# MTX_Tap_an_er_V13_Nopoti.net
KiCad netlist of a schematic drawn in EAGLE
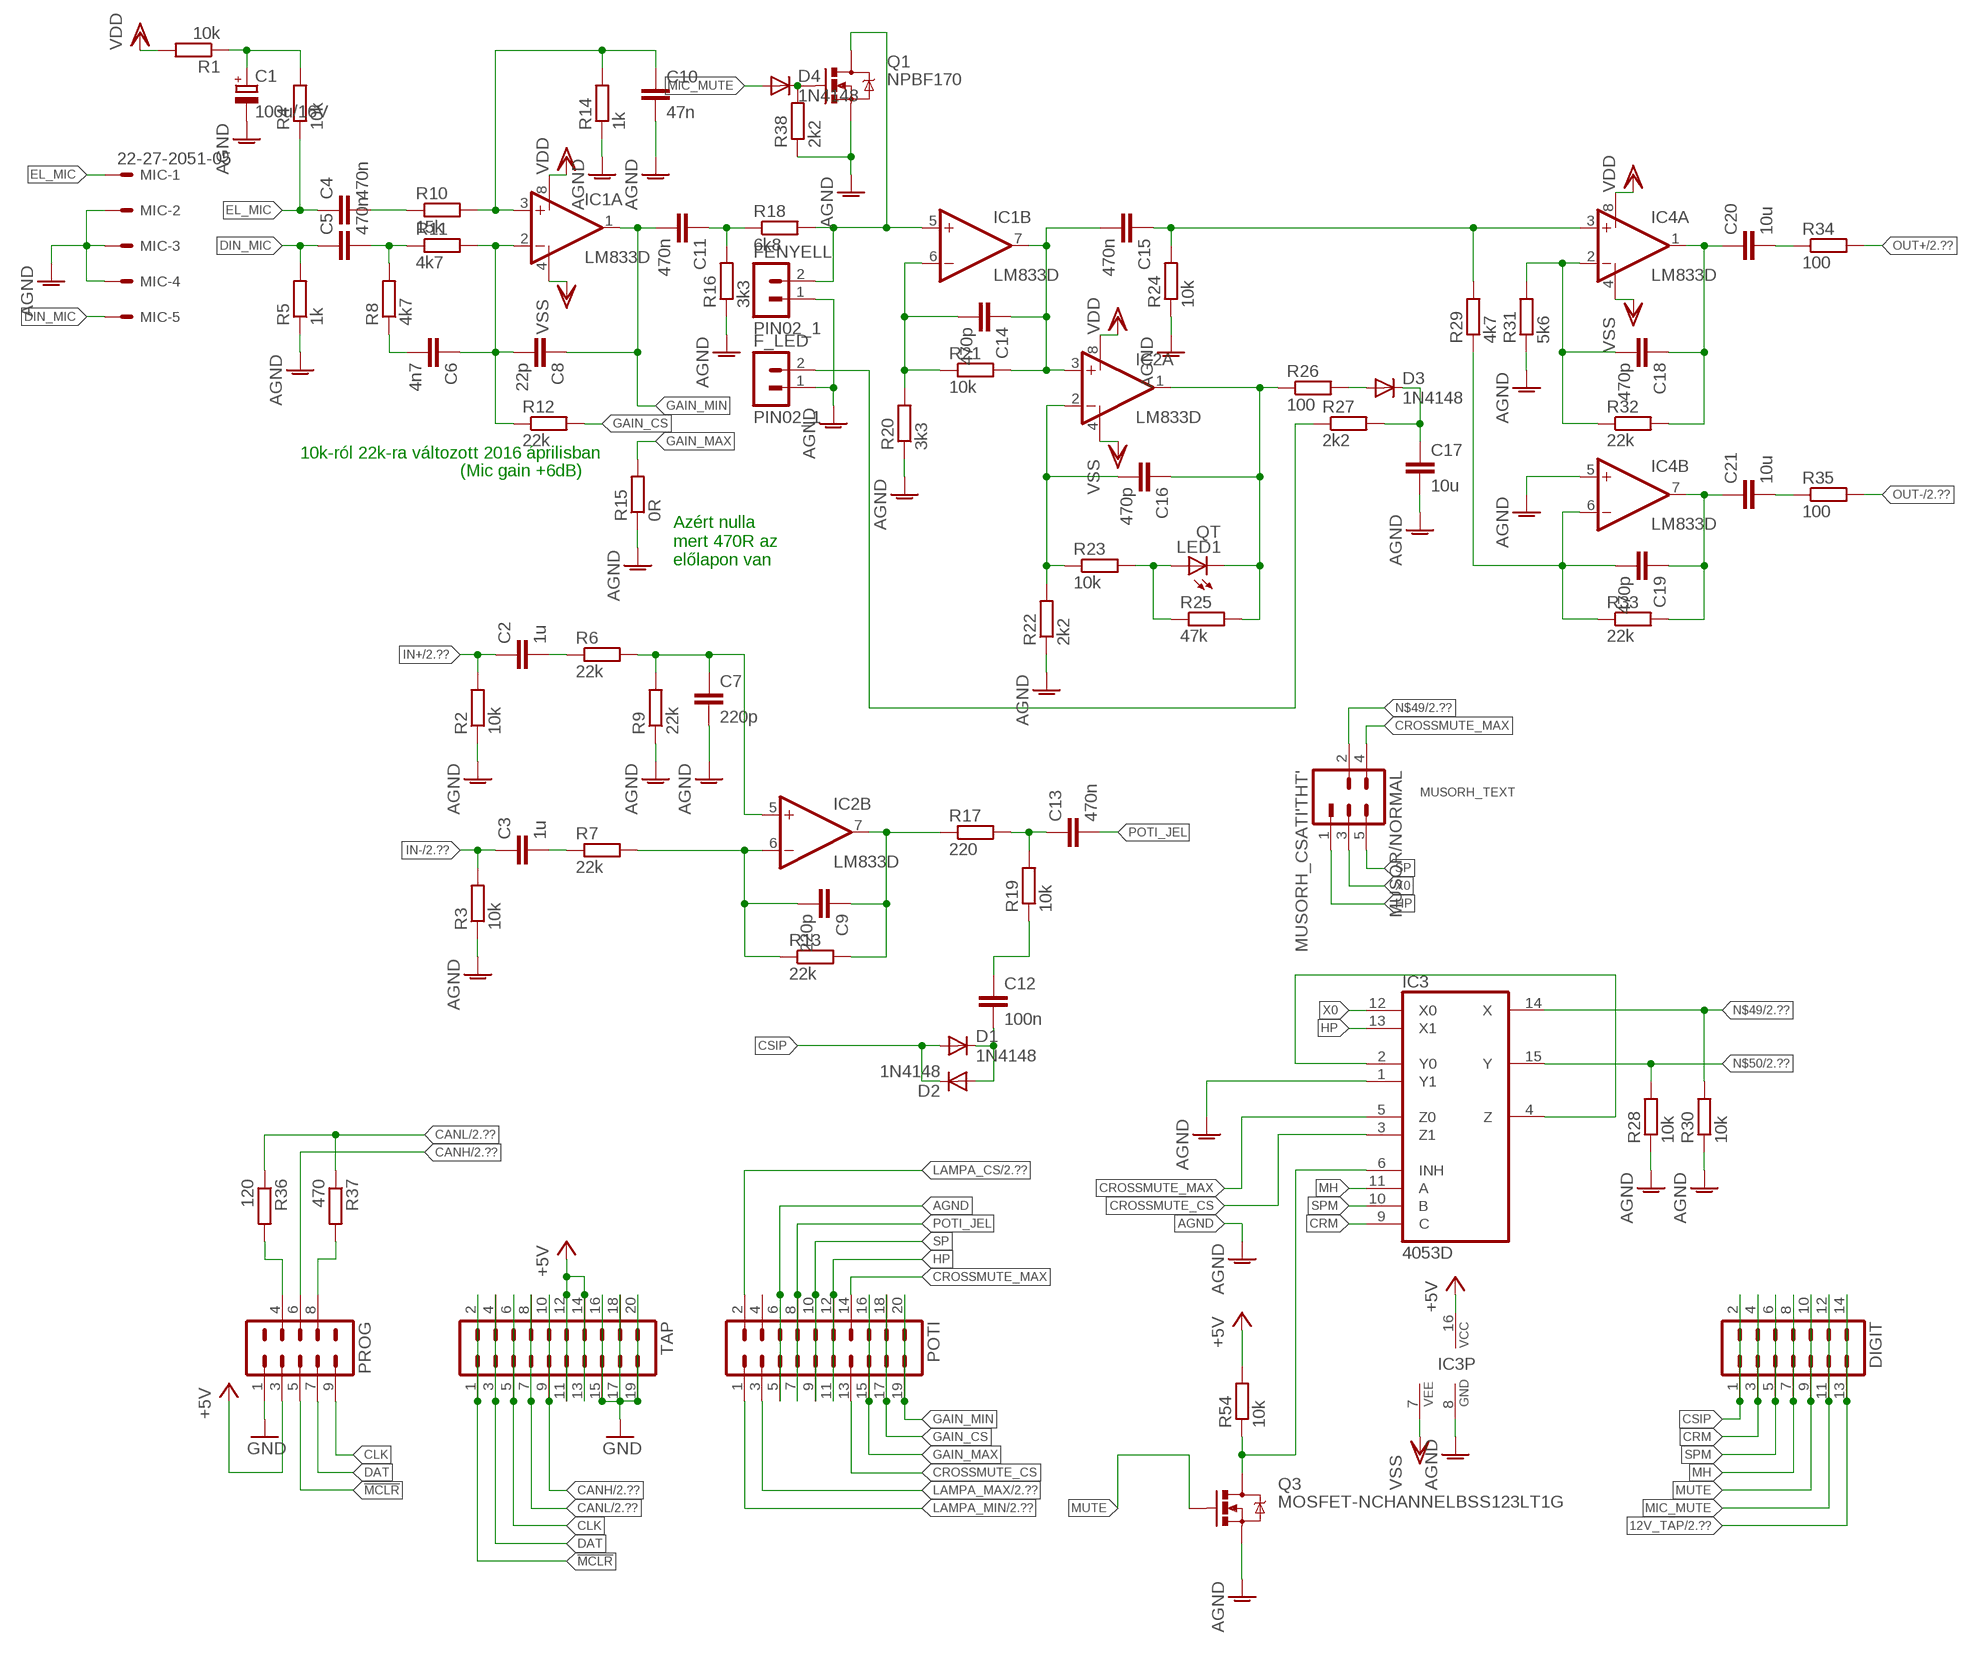
[diagram p0: schematic, sheet 1]
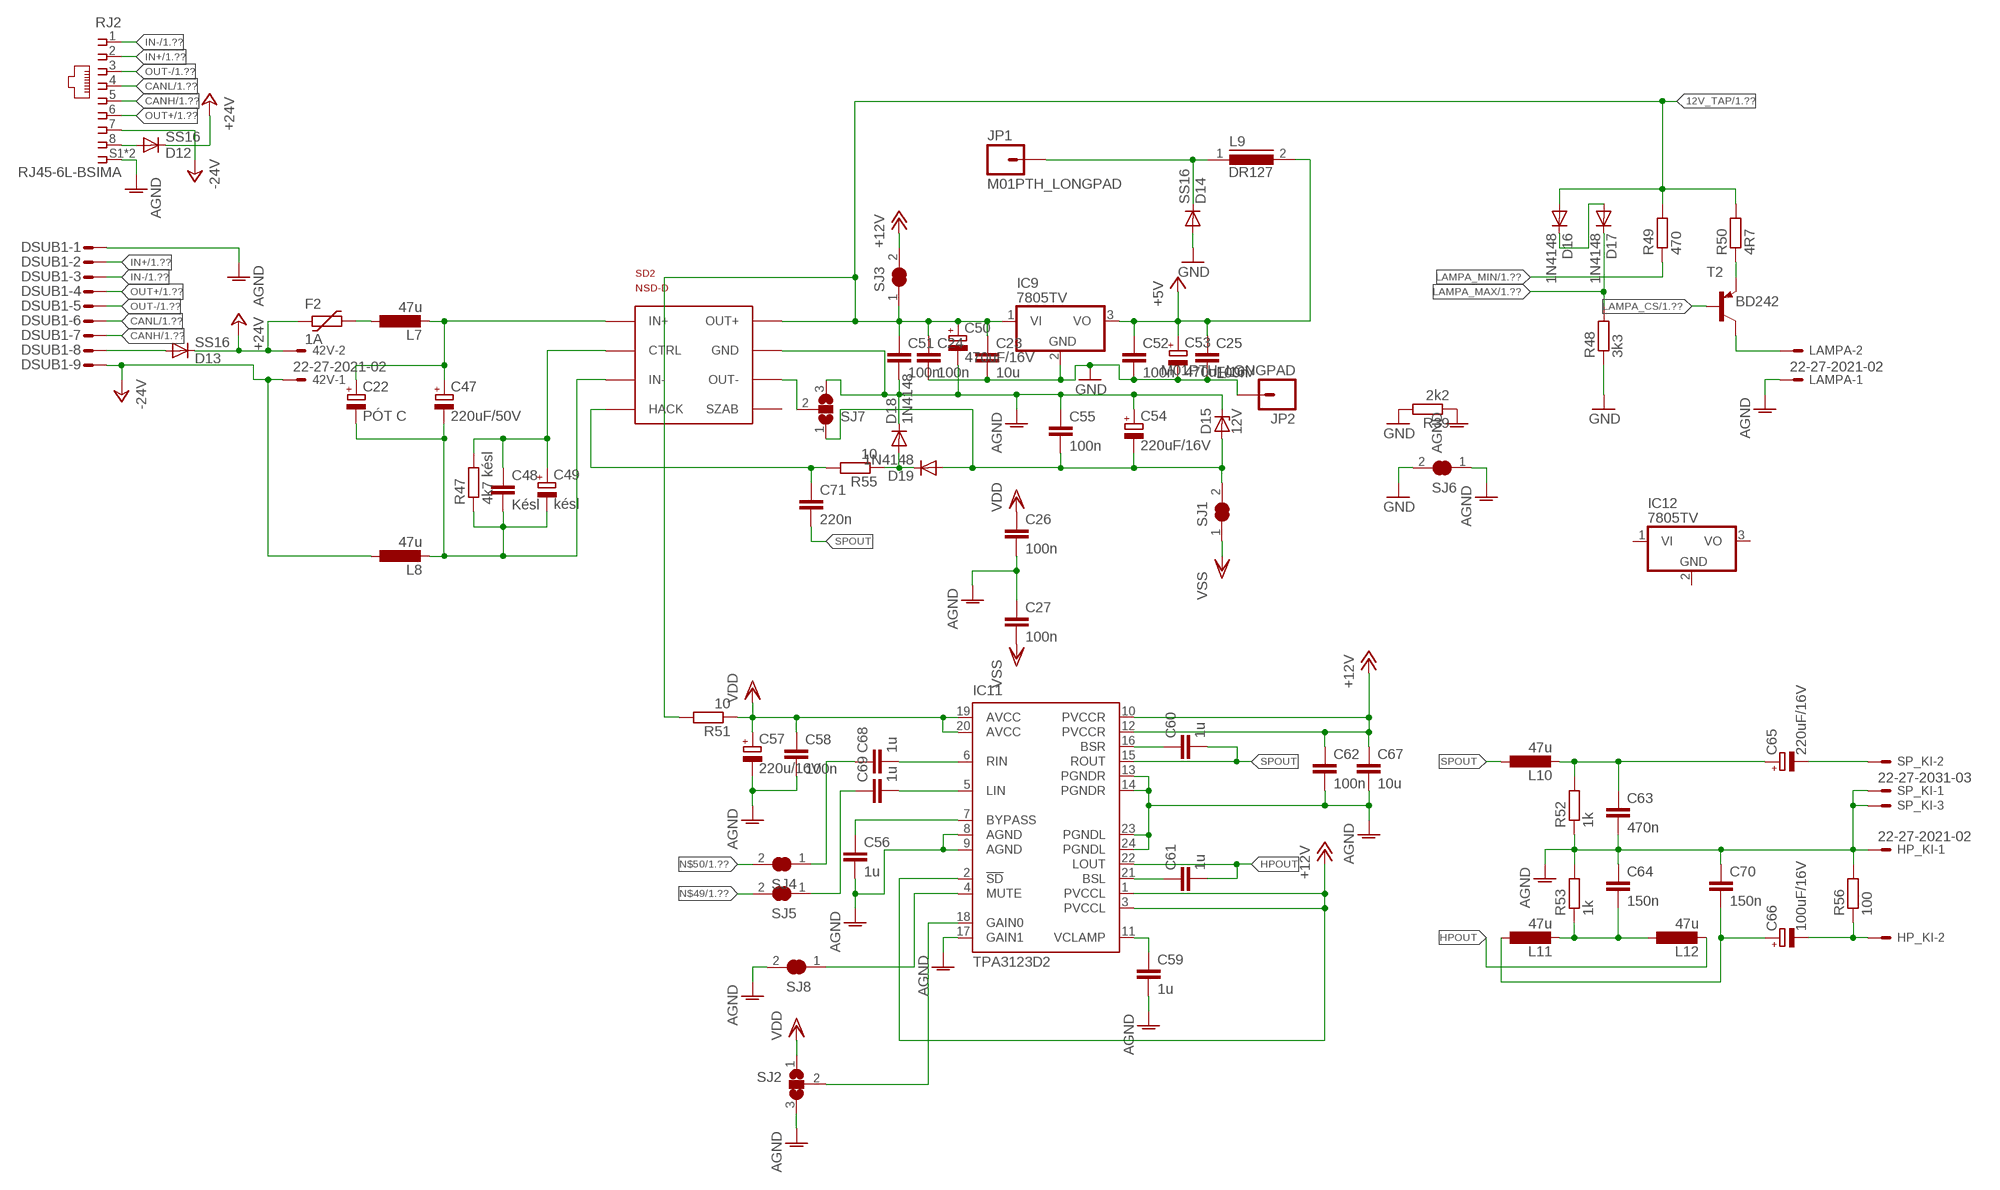
[diagram p1: schematic, sheet 2]

(export (version "E")
  (design (tool "Eeschema 10.0.6"))
  (components
    (comp (ref "42V")
      (value "22-27-2021-02")
      (footprint "eagle-import:6410-02")
      (libsource (lib "eagle-import") (part "22-?-0227-2021"))
    )
    (comp (ref "C22")
      (value "PÓT C")
      (footprint "eagle-import:E3,5-8")
      (libsource (lib "eagle-import") (part "CPOL-EUE3.5-8"))
    )
    (comp (ref "C23")
      (value "10u")
      (footprint "eagle-import:C0805")
      (libsource (lib "eagle-import") (part "C-EUC0805"))
    )
    (comp (ref "C24")
      (value "100n")
      (footprint "eagle-import:C0805")
      (libsource (lib "eagle-import") (part "C-EUC0805"))
    )
    (comp (ref "C25")
      (value "100n")
      (footprint "eagle-import:C0805")
      (libsource (lib "eagle-import") (part "C-EUC0805"))
    )
    (comp (ref "C26")
      (value "100n")
      (footprint "eagle-import:C0805")
      (libsource (lib "eagle-import") (part "C-EUC0805"))
    )
    (comp (ref "C27")
      (value "100n")
      (footprint "eagle-import:C0805")
      (libsource (lib "eagle-import") (part "C-EUC0805"))
    )
    (comp (ref "C47")
      (value "220uF/50V")
      (footprint "eagle-import:E3,5-8")
      (libsource (lib "eagle-import") (part "CPOL-EUE3.5-8"))
    )
    (comp (ref "C48")
      (value "Késl")
      (footprint "eagle-import:C0805")
      (libsource (lib "eagle-import") (part "C-EUC0805"))
    )
    (comp (ref "C49")
      (value "késl")
      (footprint "eagle-import:E2,5-5")
      (libsource (lib "eagle-import") (part "CPOL-EUE2.5-5"))
    )
    (comp (ref "C50")
      (value "470uF/16V")
      (footprint "eagle-import:E3,5-8")
      (libsource (lib "eagle-import") (part "CPOL-EUE3.5-8"))
    )
    (comp (ref "C51")
      (value "100n")
      (footprint "eagle-import:C0805")
      (libsource (lib "eagle-import") (part "C-EUC0805"))
    )
    (comp (ref "C52")
      (value "100n")
      (footprint "eagle-import:C0805")
      (libsource (lib "eagle-import") (part "C-EUC0805"))
    )
    (comp (ref "C53")
      (value "470uF/16V")
      (footprint "eagle-import:E3,5-8")
      (libsource (lib "eagle-import") (part "CPOL-EUE3.5-8"))
    )
    (comp (ref "C54")
      (value "220uF/16V")
      (footprint "eagle-import:E2,5-7")
      (libsource (lib "eagle-import") (part "CPOL-EUE2.5-7"))
    )
    (comp (ref "C55")
      (value "100n")
      (footprint "eagle-import:C0805")
      (libsource (lib "eagle-import") (part "C-EUC0805"))
    )
    (comp (ref "C56")
      (value "1u")
      (footprint "eagle-import:C0805")
      (libsource (lib "eagle-import") (part "C-EUC0805"))
    )
    (comp (ref "C57")
      (value "220u/16V")
      (footprint "eagle-import:E2,5-7")
      (libsource (lib "eagle-import") (part "CPOL-EUE2.5-7"))
    )
    (comp (ref "C58")
      (value "100n")
      (footprint "eagle-import:C0805")
      (libsource (lib "eagle-import") (part "C-EUC0805"))
    )
    (comp (ref "C59")
      (value "1u")
      (footprint "eagle-import:C0805")
      (libsource (lib "eagle-import") (part "C-EUC0805"))
    )
    (comp (ref "C60")
      (value "1u")
      (footprint "eagle-import:C0805")
      (libsource (lib "eagle-import") (part "C-EUC0805"))
    )
    (comp (ref "C61")
      (value "1u")
      (footprint "eagle-import:C0805")
      (libsource (lib "eagle-import") (part "C-EUC0805"))
    )
    (comp (ref "C62")
      (value "100n")
      (footprint "eagle-import:C0805")
      (libsource (lib "eagle-import") (part "C-EUC0805"))
    )
    (comp (ref "C63")
      (value "470n")
      (footprint "eagle-import:C0805")
      (libsource (lib "eagle-import") (part "C-EUC0805"))
    )
    (comp (ref "C64")
      (value "150n")
      (footprint "eagle-import:C0805")
      (libsource (lib "eagle-import") (part "C-EUC0805"))
    )
    (comp (ref "C65")
      (value "220uF/16V")
      (footprint "eagle-import:E2,5-7")
      (libsource (lib "eagle-import") (part "CPOL-EUE2.5-7"))
    )
    (comp (ref "C66")
      (value "100uF/16V")
      (footprint "eagle-import:E2,5-6")
      (libsource (lib "eagle-import") (part "CPOL-EUE2.5-6"))
    )
    (comp (ref "C67")
      (value "10u")
      (footprint "eagle-import:C0805")
      (libsource (lib "eagle-import") (part "C-EUC0805"))
    )
    (comp (ref "C68")
      (value "1u")
      (footprint "eagle-import:C0805")
      (libsource (lib "eagle-import") (part "C-EUC0805"))
    )
    (comp (ref "C69")
      (value "1u")
      (footprint "eagle-import:C0805")
      (libsource (lib "eagle-import") (part "C-EUC0805"))
    )
    (comp (ref "C70")
      (value "150n")
      (footprint "eagle-import:C0805")
      (libsource (lib "eagle-import") (part "C-EUC0805"))
    )
    (comp (ref "C71")
      (value "220n")
      (footprint "eagle-import:C0805")
      (libsource (lib "eagle-import") (part "C-EUC0805"))
    )
    (comp (ref "D12")
      (value "SS16")
      (footprint "eagle-import:DO-214AC")
      (libsource (lib "eagle-import") (part "dp_devices_DIODE-DO-214AC"))
    )
    (comp (ref "D13")
      (value "SS16")
      (footprint "eagle-import:DO-214AC")
      (libsource (lib "eagle-import") (part "dp_devices_DIODE-DO-214AC"))
    )
    (comp (ref "D14")
      (value "SS16")
      (footprint "eagle-import:DO-214AC")
      (libsource (lib "eagle-import") (part "dp_devices_DIODE-DO-214AC"))
    )
    (comp (ref "D15")
      (value "12V")
      (footprint "eagle-import:SOD80C")
      (libsource (lib "eagle-import") (part "ZENER-DIODESOD80C"))
    )
    (comp (ref "D16")
      (value "1N4148")
      (footprint "eagle-import:SOD80C")
      (libsource (lib "eagle-import") (part "DIODE-SOD80C"))
    )
    (comp (ref "D17")
      (value "1N4148")
      (footprint "eagle-import:SOD80C")
      (libsource (lib "eagle-import") (part "DIODE-SOD80C"))
    )
    (comp (ref "D18")
      (value "1N4148")
      (footprint "eagle-import:SOD80C")
      (libsource (lib "eagle-import") (part "DIODE-SOD80C"))
    )
    (comp (ref "D19")
      (value "1N4148")
      (footprint "eagle-import:SOD80C")
      (libsource (lib "eagle-import") (part "DIODE-SOD80C"))
    )
    (comp (ref "DSUB1")
      (value "M09-182S")
      (footprint "eagle-import:182-009-MALE")
      (libsource (lib "eagle-import") (part "M09?S-182"))
    )
    (comp (ref "F2")
      (value "1A")
      (footprint "eagle-import:PTC1812L")
      (libsource (lib "eagle-import") (part "FUSE_PTC-1812"))
    )
    (comp (ref "HP_KI")
      (value "22-27-2021-02")
      (footprint "eagle-import:6410-02")
      (libsource (lib "eagle-import") (part "22-?-0227-2021"))
    )
    (comp (ref "IC9")
      (value "7805TV")
      (footprint "eagle-import:TO220V")
      (libsource (lib "eagle-import") (part "78TV05"))
    )
    (comp (ref "IC11")
      (value "TPA3123D2")
      (footprint "eagle-import:PWP-TSSOP24")
      (fields (field (name "MPN") "TPA3123D2PWP"))
      (libsource (lib "eagle-import") (part "TPA3123D2"))
    )
    (comp (ref "IC12")
      (value "7805TV")
      (footprint "eagle-import:TO220V")
      (libsource (lib "eagle-import") (part "78TV05"))
    )
    (comp (ref "JP1")
      (value "M01PTH_LONGPAD")
      (footprint "eagle-import:1X01_LONGPAD")
      (libsource (lib "eagle-import") (part "M01PTH_LONGPAD"))
    )
    (comp (ref "JP2")
      (value "M01PTH_LONGPAD")
      (footprint "eagle-import:1X01_LONGPAD")
      (libsource (lib "eagle-import") (part "M01PTH_LONGPAD"))
    )
    (comp (ref "L7")
      (value "47u")
      (footprint "eagle-import:PIS2816")
      (libsource (lib "eagle-import") (part "L-EUPIS2816"))
    )
    (comp (ref "L8")
      (value "47u")
      (footprint "eagle-import:PIS2816")
      (libsource (lib "eagle-import") (part "L-EUPIS2816"))
    )
    (comp (ref "L9")
      (value "DR127")
      (footprint "eagle-import:DR127")
      (libsource (lib "eagle-import") (part "DR127"))
    )
    (comp (ref "L10")
      (value "47u")
      (footprint "eagle-import:PIS2816")
      (libsource (lib "eagle-import") (part "L-EUPIS2816"))
    )
    (comp (ref "L11")
      (value "47u")
      (footprint "eagle-import:PIS2816")
      (libsource (lib "eagle-import") (part "L-EUPIS2816"))
    )
    (comp (ref "L12")
      (value "47u")
      (footprint "eagle-import:PIS2816")
      (libsource (lib "eagle-import") (part "L-EUPIS2816"))
    )
    (comp (ref "LAMPA")
      (value "22-27-2021-02")
      (footprint "eagle-import:6410-02")
      (libsource (lib "eagle-import") (part "22-?-0227-2021"))
    )
    (comp (ref "R39")
      (value "2k2")
      (footprint "eagle-import:R0805")
      (libsource (lib "eagle-import") (part "R-EU_R0805"))
    )
    (comp (ref "R47")
      (value "4k7 késl")
      (footprint "eagle-import:R0805")
      (libsource (lib "eagle-import") (part "R-EU_R0805"))
    )
    (comp (ref "R48")
      (value "3k3")
      (footprint "eagle-import:R0805")
      (libsource (lib "eagle-import") (part "R-EU_R0805"))
    )
    (comp (ref "R49")
      (value "470")
      (footprint "eagle-import:R0805")
      (libsource (lib "eagle-import") (part "R-EU_R0805"))
    )
    (comp (ref "R50")
      (value "4R7")
      (footprint "eagle-import:R0805")
      (libsource (lib "eagle-import") (part "R-EU_R0805"))
    )
    (comp (ref "R51")
      (value "10")
      (footprint "eagle-import:R1210")
      (libsource (lib "eagle-import") (part "R-EU_R1210"))
    )
    (comp (ref "R52")
      (value "1k")
      (footprint "eagle-import:R0805")
      (libsource (lib "eagle-import") (part "R-EU_R0805"))
    )
    (comp (ref "R53")
      (value "1k")
      (footprint "eagle-import:R0805")
      (libsource (lib "eagle-import") (part "R-EU_R0805"))
    )
    (comp (ref "R55")
      (value "10")
      (footprint "eagle-import:R0805")
      (libsource (lib "eagle-import") (part "R-EU_R0805"))
    )
    (comp (ref "R56")
      (value "100")
      (footprint "eagle-import:R0805")
      (libsource (lib "eagle-import") (part "R-EU_R0805"))
    )
    (comp (ref "RJ2")
      (value "RJ45-6L-BSIMA")
      (footprint "eagle-import:RJ45")
      (fields (field (name "MPN") "RJ45-6L-B"))
      (libsource (lib "eagle-import") (part "RJ45SIMA-6L-B"))
    )
    (comp (ref "SD2")
      (value "NSD-D")
      (footprint "eagle-import:NSD-D")
      (libsource (lib "eagle-import") (part "NSD-D"))
    )
    (comp (ref "SJ1")
      (value "SOLDERJUMPER_CLOSED")
      (footprint "eagle-import:SOLDERJUMPER_CLOSEDWIRE")
      (libsource (lib "eagle-import") (part "SOLDERJUMPER_CLOSED"))
    )
    (comp (ref "SJ2")
      (value "SJ2WW12")
      (footprint "eagle-import:SJ_2W_12")
      (libsource (lib "eagle-import") (part "SJ2WW12"))
    )
    (comp (ref "SJ3")
      (value "SOLDERJUMPER_CLOSED")
      (footprint "eagle-import:SOLDERJUMPER_CLOSEDWIRE")
      (libsource (lib "eagle-import") (part "SOLDERJUMPER_CLOSED"))
    )
    (comp (ref "SJ4")
      (value "SOLDERJUMPER_CLOSED")
      (footprint "eagle-import:SOLDERJUMPER_CLOSEDWIRE")
      (libsource (lib "eagle-import") (part "SOLDERJUMPER_CLOSED"))
    )
    (comp (ref "SJ5")
      (value "SOLDERJUMPER_CLOSED")
      (footprint "eagle-import:SOLDERJUMPER_CLOSEDWIRE")
      (libsource (lib "eagle-import") (part "SOLDERJUMPER_CLOSED"))
    )
    (comp (ref "SJ6")
      (value "SOLDERJUMPER_CLOSED")
      (footprint "eagle-import:SOLDERJUMPER_CLOSEDWIRE")
      (libsource (lib "eagle-import") (part "SOLDERJUMPER_CLOSED"))
    )
    (comp (ref "SJ7")
      (value "SJ2WW23")
      (footprint "eagle-import:SJ_2W_23")
      (libsource (lib "eagle-import") (part "SJ2WW23"))
    )
    (comp (ref "SJ8")
      (value "SOLDERJUMPER_CLOSED")
      (footprint "eagle-import:SOLDERJUMPER_CLOSEDWIRE")
      (libsource (lib "eagle-import") (part "SOLDERJUMPER_CLOSED"))
    )
    (comp (ref "SP_KI")
      (value "22-27-2031-03")
      (footprint "eagle-import:6410-03")
      (libsource (lib "eagle-import") (part "22-?-0327-2031"))
    )
    (comp (ref "T2")
      (value "BD242")
      (footprint "eagle-import:TO220V")
      (libsource (lib "eagle-import") (part "-PNP-TO220V"))
    )
    (comp (ref "C1")
      (value "100u/16V")
      (footprint "eagle-import:E2,5-5")
      (libsource (lib "eagle-import") (part "CPOL-EUE2.5-5"))
    )
    (comp (ref "C2")
      (value "1u")
      (footprint "eagle-import:C0805")
      (libsource (lib "eagle-import") (part "C-EUC0805"))
    )
    (comp (ref "C3")
      (value "1u")
      (footprint "eagle-import:C0805")
      (libsource (lib "eagle-import") (part "C-EUC0805"))
    )
    (comp (ref "C4")
      (value "470n")
      (footprint "eagle-import:C0805")
      (libsource (lib "eagle-import") (part "C-EUC0805"))
    )
    (comp (ref "C5")
      (value "470n")
      (footprint "eagle-import:C0805")
      (libsource (lib "eagle-import") (part "C-EUC0805"))
    )
    (comp (ref "C6")
      (value "4n7")
      (footprint "eagle-import:C0805")
      (libsource (lib "eagle-import") (part "C-EUC0805"))
    )
    (comp (ref "C7")
      (value "220p")
      (footprint "eagle-import:C0805")
      (libsource (lib "eagle-import") (part "C-EUC0805"))
    )
    (comp (ref "C8")
      (value "22p")
      (footprint "eagle-import:C0805")
      (libsource (lib "eagle-import") (part "C-EUC0805"))
    )
    (comp (ref "C9")
      (value "220p")
      (footprint "eagle-import:C0805")
      (libsource (lib "eagle-import") (part "C-EUC0805"))
    )
    (comp (ref "C10")
      (value "47n")
      (footprint "eagle-import:C0805")
      (libsource (lib "eagle-import") (part "C-EUC0805"))
    )
    (comp (ref "C11")
      (value "470n")
      (footprint "eagle-import:C0805")
      (libsource (lib "eagle-import") (part "C-EUC0805"))
    )
    (comp (ref "C12")
      (value "100n")
      (footprint "eagle-import:C0805")
      (libsource (lib "eagle-import") (part "C-EUC0805"))
    )
    (comp (ref "C13")
      (value "470n")
      (footprint "eagle-import:C0805")
      (libsource (lib "eagle-import") (part "C-EUC0805"))
    )
    (comp (ref "C14")
      (value "470p")
      (footprint "eagle-import:C0805")
      (libsource (lib "eagle-import") (part "C-EUC0805"))
    )
    (comp (ref "C15")
      (value "470n")
      (footprint "eagle-import:C0805")
      (libsource (lib "eagle-import") (part "C-EUC0805"))
    )
    (comp (ref "C16")
      (value "470p")
      (footprint "eagle-import:C0805")
      (libsource (lib "eagle-import") (part "C-EUC0805"))
    )
    (comp (ref "C17")
      (value "10u")
      (footprint "eagle-import:C0805")
      (libsource (lib "eagle-import") (part "C-EUC0805"))
    )
    (comp (ref "C18")
      (value "470p")
      (footprint "eagle-import:C0805")
      (libsource (lib "eagle-import") (part "C-EUC0805"))
    )
    (comp (ref "C19")
      (value "470p")
      (footprint "eagle-import:C0805")
      (libsource (lib "eagle-import") (part "C-EUC0805"))
    )
    (comp (ref "C20")
      (value "10u")
      (footprint "eagle-import:C0805")
      (libsource (lib "eagle-import") (part "C-EUC0805"))
    )
    (comp (ref "C21")
      (value "10u")
      (footprint "eagle-import:C0805")
      (libsource (lib "eagle-import") (part "C-EUC0805"))
    )
    (comp (ref "D1")
      (value "1N4148")
      (footprint "eagle-import:SOD80C")
      (libsource (lib "eagle-import") (part "DIODE-SOD80C"))
    )
    (comp (ref "D2")
      (value "1N4148")
      (footprint "eagle-import:SOD80C")
      (libsource (lib "eagle-import") (part "DIODE-SOD80C"))
    )
    (comp (ref "D3")
      (value "1N4148")
      (footprint "eagle-import:SOD80C")
      (libsource (lib "eagle-import") (part "DIODE-SOD80C"))
    )
    (comp (ref "D4")
      (value "1N4148")
      (footprint "eagle-import:SOD80C")
      (libsource (lib "eagle-import") (part "DIODE-SOD80C"))
    )
    (comp (ref "DIGIT")
      (value "MA07-2")
      (footprint "eagle-import:MA07-2")
      (libsource (lib "eagle-import") (part "MA07-2"))
    )
    (comp (ref "FENYELL")
      (value "PIN02_1")
      (footprint "eagle-import:PIN02_1")
      (libsource (lib "eagle-import") (part "PIN02_1"))
    )
    (comp (ref "F_LED")
      (value "PIN02_1")
      (footprint "eagle-import:PIN02_1")
      (libsource (lib "eagle-import") (part "PIN02_1"))
    )
    (comp (ref "IC1")
      (value "LM833D")
      (footprint "eagle-import:SO08")
      (libsource (lib "eagle-import") (part "LM833D"))
    )
    (comp (ref "IC2")
      (value "LM833D")
      (footprint "eagle-import:SO08")
      (libsource (lib "eagle-import") (part "LM833D"))
    )
    (comp (ref "IC3")
      (value "4053D")
      (footprint "eagle-import:SO16")
      (libsource (lib "eagle-import") (part "4053D"))
    )
    (comp (ref "IC4")
      (value "LM833D")
      (footprint "eagle-import:SO08")
      (libsource (lib "eagle-import") (part "LM833D"))
    )
    (comp (ref "LED1")
      (value "QT")
      (footprint "eagle-import:LED3MM")
      (libsource (lib "eagle-import") (part "LED3MM"))
    )
    (comp (ref "MIC")
      (value "22-27-2051-05")
      (footprint "eagle-import:6410-05")
      (libsource (lib "eagle-import") (part "22-?-0527-2051"))
    )
    (comp (ref "MUSOR/NORMAL")
      (value "MUSORH_CSATI'THT'")
      (footprint "eagle-import:MUSORH_CSATI")
      (libsource (lib "eagle-import") (part "MUSORH_CSATI'THT'"))
    )
    (comp (ref "POTI")
      (value "MA10-2")
      (footprint "eagle-import:MA10-2")
      (libsource (lib "eagle-import") (part "MA10-2"))
    )
    (comp (ref "PROG")
      (value "CN_CANTAN")
      (footprint "eagle-import:CN_CANTAN")
      (libsource (lib "eagle-import") (part "CN_CANTAN"))
    )
    (comp (ref "Q1")
      (value "NPBF170")
      (footprint "eagle-import:SOT23")
      (libsource (lib "eagle-import") (part "MOSFET-NCHANNELBSS138"))
    )
    (comp (ref "Q3")
      (value "MOSFET-NCHANNELBSS123LT1G")
      (footprint "eagle-import:SOT23")
      (libsource (lib "eagle-import") (part "MOSFET-NCHANNELBSS123LT1G"))
    )
    (comp (ref "R1")
      (value "10k")
      (footprint "eagle-import:R0805")
      (libsource (lib "eagle-import") (part "R-EU_R0805"))
    )
    (comp (ref "R2")
      (value "10k")
      (footprint "eagle-import:R0805")
      (libsource (lib "eagle-import") (part "R-EU_R0805"))
    )
    (comp (ref "R3")
      (value "10k")
      (footprint "eagle-import:R0805")
      (libsource (lib "eagle-import") (part "R-EU_R0805"))
    )
    (comp (ref "R4")
      (value "10k")
      (footprint "eagle-import:R0805")
      (libsource (lib "eagle-import") (part "R-EU_R0805"))
    )
    (comp (ref "R5")
      (value "1k")
      (footprint "eagle-import:R0805")
      (libsource (lib "eagle-import") (part "R-EU_R0805"))
    )
    (comp (ref "R6")
      (value "22k")
      (footprint "eagle-import:R0805")
      (libsource (lib "eagle-import") (part "R-EU_R0805"))
    )
    (comp (ref "R7")
      (value "22k")
      (footprint "eagle-import:R0805")
      (libsource (lib "eagle-import") (part "R-EU_R0805"))
    )
    (comp (ref "R8")
      (value "4k7")
      (footprint "eagle-import:R0805")
      (libsource (lib "eagle-import") (part "R-EU_R0805"))
    )
    (comp (ref "R9")
      (value "22k")
      (footprint "eagle-import:R0805")
      (libsource (lib "eagle-import") (part "R-EU_R0805"))
    )
    (comp (ref "R10")
      (value "15k")
      (footprint "eagle-import:R0805")
      (libsource (lib "eagle-import") (part "R-EU_R0805"))
    )
    (comp (ref "R11")
      (value "4k7")
      (footprint "eagle-import:R0805")
      (libsource (lib "eagle-import") (part "R-EU_R0805"))
    )
    (comp (ref "R12")
      (value "22k")
      (footprint "eagle-import:R0805")
      (libsource (lib "eagle-import") (part "R-EU_R0805"))
    )
    (comp (ref "R13")
      (value "22k")
      (footprint "eagle-import:R0805")
      (libsource (lib "eagle-import") (part "R-EU_R0805"))
    )
    (comp (ref "R14")
      (value "1k")
      (footprint "eagle-import:R0805")
      (libsource (lib "eagle-import") (part "R-EU_R0805"))
    )
    (comp (ref "R15")
      (value "0R")
      (footprint "eagle-import:R0805")
      (libsource (lib "eagle-import") (part "R-EU_R0805"))
    )
    (comp (ref "R16")
      (value "3k3")
      (footprint "eagle-import:R0805")
      (libsource (lib "eagle-import") (part "R-EU_R0805"))
    )
    (comp (ref "R17")
      (value "220")
      (footprint "eagle-import:R0805")
      (libsource (lib "eagle-import") (part "R-EU_R0805"))
    )
    (comp (ref "R18")
      (value "6k8")
      (footprint "eagle-import:R0805")
      (libsource (lib "eagle-import") (part "R-EU_R0805"))
    )
    (comp (ref "R19")
      (value "10k")
      (footprint "eagle-import:R0805")
      (libsource (lib "eagle-import") (part "R-EU_R0805"))
    )
    (comp (ref "R20")
      (value "3k3")
      (footprint "eagle-import:R0805")
      (libsource (lib "eagle-import") (part "R-EU_R0805"))
    )
    (comp (ref "R21")
      (value "10k")
      (footprint "eagle-import:R0805")
      (libsource (lib "eagle-import") (part "R-EU_R0805"))
    )
    (comp (ref "R22")
      (value "2k2")
      (footprint "eagle-import:R0805")
      (libsource (lib "eagle-import") (part "R-EU_R0805"))
    )
    (comp (ref "R23")
      (value "10k")
      (footprint "eagle-import:R0805")
      (libsource (lib "eagle-import") (part "R-EU_R0805"))
    )
    (comp (ref "R24")
      (value "10k")
      (footprint "eagle-import:R0805")
      (libsource (lib "eagle-import") (part "R-EU_R0805"))
    )
    (comp (ref "R25")
      (value "47k")
      (footprint "eagle-import:R0805")
      (libsource (lib "eagle-import") (part "R-EU_R0805"))
    )
    (comp (ref "R26")
      (value "100")
      (footprint "eagle-import:R0805")
      (libsource (lib "eagle-import") (part "R-EU_R0805"))
    )
    (comp (ref "R27")
      (value "2k2")
      (footprint "eagle-import:R0805")
      (libsource (lib "eagle-import") (part "R-EU_R0805"))
    )
    (comp (ref "R28")
      (value "10k")
      (footprint "eagle-import:R0805")
      (libsource (lib "eagle-import") (part "R-EU_R0805"))
    )
    (comp (ref "R29")
      (value "4k7")
      (footprint "eagle-import:R0805")
      (libsource (lib "eagle-import") (part "R-EU_R0805"))
    )
    (comp (ref "R30")
      (value "10k")
      (footprint "eagle-import:R0805")
      (libsource (lib "eagle-import") (part "R-EU_R0805"))
    )
    (comp (ref "R31")
      (value "5k6")
      (footprint "eagle-import:R0805")
      (libsource (lib "eagle-import") (part "R-EU_R0805"))
    )
    (comp (ref "R32")
      (value "22k")
      (footprint "eagle-import:R0805")
      (libsource (lib "eagle-import") (part "R-EU_R0805"))
    )
    (comp (ref "R33")
      (value "22k")
      (footprint "eagle-import:R0805")
      (libsource (lib "eagle-import") (part "R-EU_R0805"))
    )
    (comp (ref "R34")
      (value "100")
      (footprint "eagle-import:R0805")
      (libsource (lib "eagle-import") (part "R-EU_R0805"))
    )
    (comp (ref "R35")
      (value "100")
      (footprint "eagle-import:R0805")
      (libsource (lib "eagle-import") (part "R-EU_R0805"))
    )
    (comp (ref "R36")
      (value "120")
      (footprint "eagle-import:R0805")
      (libsource (lib "eagle-import") (part "R-EU_R0805"))
    )
    (comp (ref "R37")
      (value "470")
      (footprint "eagle-import:R0805")
      (libsource (lib "eagle-import") (part "R-EU_R0805"))
    )
    (comp (ref "R38")
      (value "2k2")
      (footprint "eagle-import:R0805")
      (libsource (lib "eagle-import") (part "R-EU_R0805"))
    )
    (comp (ref "R54")
      (value "10k")
      (footprint "eagle-import:R0805")
      (libsource (lib "eagle-import") (part "R-EU_R0805"))
    )
    (comp (ref "TAP")
      (value "MA10-2")
      (footprint "eagle-import:MA10-2")
      (libsource (lib "eagle-import") (part "MA10-2"))
    )
    (comp (ref "U$1")
      (value "MUSORH_TEXT")
      (footprint "eagle-import:MUSORH_TEXT")
      (libsource (lib "eagle-import") (part "MUSORH_TEXT"))
    )
  )
  (nets
    (net (code "1") (name "+5V") (class "Default")
      (node (ref "C25") (pin "1") (pinfunction "1_1") (pintype "passive"))
      (node (ref "C52") (pin "1") (pinfunction "1_1") (pintype "passive"))
      (node (ref "C53") (pin "+") (pinfunction "+_+") (pintype "passive"))
      (node (ref "IC3") (pin "16") (pinfunction "VCC_16") (pintype "power_in"))
      (node (ref "IC9") (pin "3") (pinfunction "VO_3") (pintype "passive"))
      (node (ref "L9") (pin "2") (pinfunction "2_2") (pintype "passive"))
      (node (ref "PROG") (pin "3") (pinfunction "3_3") (pintype "passive"))
      (node (ref "R54") (pin "2") (pinfunction "2_2") (pintype "passive"))
      (node (ref "TAP") (pin "11") (pinfunction "11_11") (pintype "passive"))
      (node (ref "TAP") (pin "12") (pinfunction "12_12") (pintype "passive"))
      (node (ref "TAP") (pin "13") (pinfunction "13_13") (pintype "passive"))
      (node (ref "TAP") (pin "14") (pinfunction "14_14") (pintype "passive"))
    )
    (net (code "2") (name "+12V") (class "Default")
      (node (ref "C62") (pin "1") (pinfunction "1_1") (pintype "passive"))
      (node (ref "C67") (pin "1") (pinfunction "1_1") (pintype "passive"))
      (node (ref "IC11") (pin "1") (pinfunction "PVCCL_1") (pintype "input"))
      (node (ref "IC11") (pin "10") (pinfunction "PVCCR_10") (pintype "input"))
      (node (ref "IC11") (pin "12") (pinfunction "PVCCR_12") (pintype "input"))
      (node (ref "IC11") (pin "2") (pinfunction "~{SD}_2") (pintype "input"))
      (node (ref "IC11") (pin "3") (pinfunction "PVCCL_3") (pintype "input"))
      (node (ref "SJ3") (pin "2") (pinfunction "2_2") (pintype "passive"))
    )
    (net (code "3") (name "+24V") (class "Default")
      (node (ref "42V") (pin "2") (pinfunction "S_2") (pintype "passive"))
      (node (ref "D12") (pin "1") (pinfunction "C_1") (pintype "passive"))
      (node (ref "D13") (pin "1") (pinfunction "C_1") (pintype "passive"))
      (node (ref "F2") (pin "1") (pinfunction "1_1") (pintype "passive"))
    )
    (net (code "4") (name "-24V") (class "Default")
      (node (ref "42V") (pin "1") (pinfunction "S_1") (pintype "passive"))
      (node (ref "DSUB1") (pin "9") (pinfunction "M_9") (pintype "passive"))
      (node (ref "L8") (pin "1") (pinfunction "1_1") (pintype "passive"))
      (node (ref "RJ2") (pin "7") (pinfunction "7_7") (pintype "passive"))
    )
    (net (code "5") (name "12V_TAP") (class "Default")
      (node (ref "C23") (pin "1") (pinfunction "1_1") (pintype "passive"))
      (node (ref "C24") (pin "1") (pinfunction "1_1") (pintype "passive"))
      (node (ref "C50") (pin "+") (pinfunction "+_+") (pintype "passive"))
      (node (ref "C51") (pin "1") (pinfunction "1_1") (pintype "passive"))
      (node (ref "D16") (pin "A") (pinfunction "A_A") (pintype "passive"))
      (node (ref "DIGIT") (pin "13") (pinfunction "13_13") (pintype "passive"))
      (node (ref "DIGIT") (pin "14") (pinfunction "14_14") (pintype "passive"))
      (node (ref "IC9") (pin "1") (pinfunction "VI_1") (pintype "input"))
      (node (ref "R49") (pin "2") (pinfunction "2_2") (pintype "passive"))
      (node (ref "R50") (pin "2") (pinfunction "2_2") (pintype "passive"))
      (node (ref "R51") (pin "2") (pinfunction "2_2") (pintype "passive"))
      (node (ref "SD2") (pin "OUT+") (pinfunction "OUT+_OUT+") (pintype "bidirectional"))
      (node (ref "SJ3") (pin "1") (pinfunction "1_1") (pintype "passive"))
    )
    (net (code "6") (name "AGND") (class "Default")
      (node (ref "C1") (pin "-") (pinfunction "-_-") (pintype "passive"))
      (node (ref "C10") (pin "2") (pinfunction "2_2") (pintype "passive"))
      (node (ref "C17") (pin "2") (pinfunction "2_2") (pintype "passive"))
      (node (ref "C26") (pin "2") (pinfunction "2_2") (pintype "passive"))
      (node (ref "C27") (pin "1") (pinfunction "1_1") (pintype "passive"))
      (node (ref "C50") (pin "-") (pinfunction "-_-") (pintype "passive"))
      (node (ref "C51") (pin "2") (pinfunction "2_2") (pintype "passive"))
      (node (ref "C54") (pin "+") (pinfunction "+_+") (pintype "passive"))
      (node (ref "C55") (pin "1") (pinfunction "1_1") (pintype "passive"))
      (node (ref "C56") (pin "2") (pinfunction "2_2") (pintype "passive"))
      (node (ref "C57") (pin "-") (pinfunction "-_-") (pintype "passive"))
      (node (ref "C58") (pin "2") (pinfunction "2_2") (pintype "passive"))
      (node (ref "C59") (pin "2") (pinfunction "2_2") (pintype "passive"))
      (node (ref "C62") (pin "2") (pinfunction "2_2") (pintype "passive"))
      (node (ref "C63") (pin "2") (pinfunction "2_2") (pintype "passive"))
      (node (ref "C64") (pin "1") (pinfunction "1_1") (pintype "passive"))
      (node (ref "C67") (pin "2") (pinfunction "2_2") (pintype "passive"))
      (node (ref "C7") (pin "2") (pinfunction "2_2") (pintype "passive"))
      (node (ref "C70") (pin "1") (pinfunction "1_1") (pintype "passive"))
      (node (ref "D15") (pin "C") (pinfunction "C_C") (pintype "passive"))
      (node (ref "D18") (pin "C") (pinfunction "C_C") (pintype "passive"))
      (node (ref "DSUB1") (pin "1") (pinfunction "M_1") (pintype "passive"))
      (node (ref "FENYELL") (pin "1") (pinfunction "1_1") (pintype "passive"))
      (node (ref "F_LED") (pin "1") (pinfunction "1_1") (pintype "passive"))
      (node (ref "HP_KI") (pin "1") (pinfunction "S_1") (pintype "passive"))
      (node (ref "IC11") (pin "13") (pinfunction "PGNDR_13") (pintype "input"))
      (node (ref "IC11") (pin "14") (pinfunction "PGNDR_14") (pintype "input"))
      (node (ref "IC11") (pin "17") (pinfunction "GAIN1_17") (pintype "input"))
      (node (ref "IC11") (pin "23") (pinfunction "PGNDL_23") (pintype "input"))
      (node (ref "IC11") (pin "24") (pinfunction "PGNDL_24") (pintype "input"))
      (node (ref "IC11") (pin "8") (pinfunction "AGND_8") (pintype "input"))
      (node (ref "IC11") (pin "9") (pinfunction "AGND_9") (pintype "input"))
      (node (ref "IC3") (pin "1") (pinfunction "Y1_1") (pintype "bidirectional"))
      (node (ref "IC3") (pin "8") (pinfunction "GND_8") (pintype "power_in"))
      (node (ref "IC4") (pin "5") (pinfunction "+IN_5") (pintype "input"))
      (node (ref "LAMPA") (pin "1") (pinfunction "S_1") (pintype "passive"))
      (node (ref "MIC") (pin "2") (pinfunction "S_2") (pintype "passive"))
      (node (ref "MIC") (pin "3") (pinfunction "S_3") (pintype "passive"))
      (node (ref "MIC") (pin "4") (pinfunction "S_4") (pintype "passive"))
      (node (ref "POTI") (pin "5") (pinfunction "5_5") (pintype "passive"))
      (node (ref "POTI") (pin "6") (pinfunction "6_6") (pintype "passive"))
      (node (ref "Q1") (pin "2") (pinfunction "S_2") (pintype "passive"))
      (node (ref "Q3") (pin "2") (pinfunction "S_2") (pintype "passive"))
      (node (ref "R14") (pin "1") (pinfunction "1_1") (pintype "passive"))
      (node (ref "R15") (pin "1") (pinfunction "1_1") (pintype "passive"))
      (node (ref "R16") (pin "1") (pinfunction "1_1") (pintype "passive"))
      (node (ref "R2") (pin "1") (pinfunction "1_1") (pintype "passive"))
      (node (ref "R20") (pin "1") (pinfunction "1_1") (pintype "passive"))
      (node (ref "R22") (pin "1") (pinfunction "1_1") (pintype "passive"))
      (node (ref "R24") (pin "1") (pinfunction "1_1") (pintype "passive"))
      (node (ref "R28") (pin "1") (pinfunction "1_1") (pintype "passive"))
      (node (ref "R3") (pin "1") (pinfunction "1_1") (pintype "passive"))
      (node (ref "R30") (pin "1") (pinfunction "1_1") (pintype "passive"))
      (node (ref "R31") (pin "1") (pinfunction "1_1") (pintype "passive"))
      (node (ref "R38") (pin "1") (pinfunction "1_1") (pintype "passive"))
      (node (ref "R39") (pin "1") (pinfunction "1_1") (pintype "passive"))
      (node (ref "R5") (pin "1") (pinfunction "1_1") (pintype "passive"))
      (node (ref "R52") (pin "1") (pinfunction "1_1") (pintype "passive"))
      (node (ref "R53") (pin "2") (pinfunction "2_2") (pintype "passive"))
      (node (ref "R56") (pin "2") (pinfunction "2_2") (pintype "passive"))
      (node (ref "R9") (pin "1") (pinfunction "1_1") (pintype "passive"))
      (node (ref "RJ2") (pin "S1") (pinfunction "S_S1") (pintype "passive"))
      (node (ref "RJ2") (pin "S2") (pinfunction "S_S2") (pintype "passive"))
      (node (ref "SD2") (pin "COMMON") (pinfunction "GND_COMMON") (pintype "bidirectional"))
      (node (ref "SJ2") (pin "3") (pinfunction "3_3") (pintype "passive"))
      (node (ref "SJ6") (pin "1") (pinfunction "1_1") (pintype "passive"))
      (node (ref "SJ7") (pin "3") (pinfunction "3_3") (pintype "passive"))
      (node (ref "SJ8") (pin "2") (pinfunction "2_2") (pintype "passive"))
      (node (ref "SP_KI") (pin "1") (pinfunction "S_1") (pintype "passive"))
      (node (ref "SP_KI") (pin "3") (pinfunction "S_3") (pintype "passive"))
    )
    (net (code "7") (name "CANH") (class "Default")
      (node (ref "DSUB1") (pin "7") (pinfunction "M_7") (pintype "passive"))
      (node (ref "PROG") (pin "6") (pinfunction "6_6") (pintype "passive"))
      (node (ref "RJ2") (pin "5") (pinfunction "5_5") (pintype "passive"))
      (node (ref "TAP") (pin "10") (pinfunction "10_10") (pintype "passive"))
      (node (ref "TAP") (pin "9") (pinfunction "9_9") (pintype "passive"))
    )
    (net (code "8") (name "CANL") (class "Default")
      (node (ref "DSUB1") (pin "6") (pinfunction "M_6") (pintype "passive"))
      (node (ref "R36") (pin "1") (pinfunction "1_1") (pintype "passive"))
      (node (ref "R37") (pin "1") (pinfunction "1_1") (pintype "passive"))
      (node (ref "RJ2") (pin "4") (pinfunction "4_4") (pintype "passive"))
      (node (ref "TAP") (pin "7") (pinfunction "7_7") (pintype "passive"))
      (node (ref "TAP") (pin "8") (pinfunction "8_8") (pintype "passive"))
    )
    (net (code "9") (name "CLK") (class "Default")
      (node (ref "PROG") (pin "9") (pinfunction "9_9") (pintype "passive"))
      (node (ref "TAP") (pin "5") (pinfunction "5_5") (pintype "passive"))
      (node (ref "TAP") (pin "6") (pinfunction "6_6") (pintype "passive"))
    )
    (net (code "10") (name "CRM") (class "Default")
      (node (ref "DIGIT") (pin "3") (pinfunction "3_3") (pintype "passive"))
      (node (ref "DIGIT") (pin "4") (pinfunction "4_4") (pintype "passive"))
      (node (ref "IC3") (pin "9") (pinfunction "C_9") (pintype "input"))
    )
    (net (code "11") (name "CROSSMUTE_CS") (class "Default")
      (node (ref "IC3") (pin "3") (pinfunction "Z1_3") (pintype "bidirectional"))
      (node (ref "POTI") (pin "13") (pinfunction "13_13") (pintype "passive"))
    )
    (net (code "12") (name "CROSSMUTE_MAX") (class "Default")
      (node (ref "IC3") (pin "5") (pinfunction "Z0_5") (pintype "bidirectional"))
      (node (ref "MUSOR/NORMAL") (pin "4") (pinfunction "4_4") (pintype "passive"))
      (node (ref "POTI") (pin "14") (pinfunction "14_14") (pintype "passive"))
    )
    (net (code "13") (name "CSIP") (class "Default")
      (node (ref "D1") (pin "A") (pinfunction "A_A") (pintype "passive"))
      (node (ref "D2") (pin "C") (pinfunction "C_C") (pintype "passive"))
      (node (ref "DIGIT") (pin "1") (pinfunction "1_1") (pintype "passive"))
      (node (ref "DIGIT") (pin "2") (pinfunction "2_2") (pintype "passive"))
    )
    (net (code "14") (name "DAT") (class "Default")
      (node (ref "PROG") (pin "7") (pinfunction "7_7") (pintype "passive"))
      (node (ref "TAP") (pin "3") (pinfunction "3_3") (pintype "passive"))
      (node (ref "TAP") (pin "4") (pinfunction "4_4") (pintype "passive"))
    )
    (net (code "15") (name "DIN_MIC") (class "Default")
      (node (ref "C5") (pin "1") (pinfunction "1_1") (pintype "passive"))
      (node (ref "MIC") (pin "5") (pinfunction "S_5") (pintype "passive"))
      (node (ref "R5") (pin "2") (pinfunction "2_2") (pintype "passive"))
    )
    (net (code "16") (name "EL_MIC") (class "Default")
      (node (ref "C4") (pin "1") (pinfunction "1_1") (pintype "passive"))
      (node (ref "MIC") (pin "1") (pinfunction "S_1") (pintype "passive"))
      (node (ref "R4") (pin "1") (pinfunction "1_1") (pintype "passive"))
    )
    (net (code "17") (name "GAIN_CS") (class "Default")
      (node (ref "POTI") (pin "17") (pinfunction "17_17") (pintype "passive"))
      (node (ref "POTI") (pin "18") (pinfunction "18_18") (pintype "passive"))
      (node (ref "R12") (pin "2") (pinfunction "2_2") (pintype "passive"))
    )
    (net (code "18") (name "GAIN_MAX") (class "Default")
      (node (ref "POTI") (pin "15") (pinfunction "15_15") (pintype "passive"))
      (node (ref "POTI") (pin "16") (pinfunction "16_16") (pintype "passive"))
      (node (ref "R15") (pin "2") (pinfunction "2_2") (pintype "passive"))
    )
    (net (code "19") (name "GAIN_MIN") (class "Default")
      (node (ref "C11") (pin "2") (pinfunction "2_2") (pintype "passive"))
      (node (ref "C8") (pin "1") (pinfunction "1_1") (pintype "passive"))
      (node (ref "IC1") (pin "1") (pinfunction "OUT_1") (pintype "output"))
      (node (ref "POTI") (pin "19") (pinfunction "19_19") (pintype "passive"))
      (node (ref "POTI") (pin "20") (pinfunction "20_20") (pintype "passive"))
    )
    (net (code "20") (name "GND") (class "Default")
      (node (ref "C23") (pin "2") (pinfunction "2_2") (pintype "passive"))
      (node (ref "C24") (pin "2") (pinfunction "2_2") (pintype "passive"))
      (node (ref "C25") (pin "2") (pinfunction "2_2") (pintype "passive"))
      (node (ref "C52") (pin "2") (pinfunction "2_2") (pintype "passive"))
      (node (ref "C53") (pin "-") (pinfunction "-_-") (pintype "passive"))
      (node (ref "D14") (pin "2") (pinfunction "A_2") (pintype "passive"))
      (node (ref "IC9") (pin "2") (pinfunction "GND_2") (pintype "passive"))
      (node (ref "JP2") (pin "1") (pinfunction "1_1") (pintype "passive"))
      (node (ref "PROG") (pin "1") (pinfunction "1_1") (pintype "passive"))
      (node (ref "R39") (pin "2") (pinfunction "2_2") (pintype "passive"))
      (node (ref "R48") (pin "1") (pinfunction "1_1") (pintype "passive"))
      (node (ref "SJ6") (pin "2") (pinfunction "2_2") (pintype "passive"))
      (node (ref "TAP") (pin "15") (pinfunction "15_15") (pintype "passive"))
      (node (ref "TAP") (pin "16") (pinfunction "16_16") (pintype "passive"))
      (node (ref "TAP") (pin "17") (pinfunction "17_17") (pintype "passive"))
      (node (ref "TAP") (pin "18") (pinfunction "18_18") (pintype "passive"))
      (node (ref "TAP") (pin "19") (pinfunction "19_19") (pintype "passive"))
      (node (ref "TAP") (pin "20") (pinfunction "20_20") (pintype "passive"))
    )
    (net (code "21") (name "HP") (class "Default")
      (node (ref "IC3") (pin "13") (pinfunction "X1_13") (pintype "bidirectional"))
      (node (ref "MUSOR/NORMAL") (pin "1") (pinfunction "1_1") (pintype "passive"))
      (node (ref "POTI") (pin "11") (pinfunction "11_11") (pintype "passive"))
      (node (ref "POTI") (pin "12") (pinfunction "12_12") (pintype "passive"))
    )
    (net (code "22") (name "HPOUT") (class "Default")
      (node (ref "C61") (pin "2") (pinfunction "2_2") (pintype "passive"))
      (node (ref "IC11") (pin "22") (pinfunction "LOUT_22") (pintype "output"))
      (node (ref "L12") (pin "2") (pinfunction "2_2") (pintype "passive"))
    )
    (net (code "23") (name "IN+") (class "Default")
      (node (ref "C2") (pin "1") (pinfunction "1_1") (pintype "passive"))
      (node (ref "DSUB1") (pin "2") (pinfunction "M_2") (pintype "passive"))
      (node (ref "R2") (pin "2") (pinfunction "2_2") (pintype "passive"))
      (node (ref "RJ2") (pin "2") (pinfunction "2_2") (pintype "passive"))
    )
    (net (code "24") (name "IN-") (class "Default")
      (node (ref "C3") (pin "1") (pinfunction "1_1") (pintype "passive"))
      (node (ref "DSUB1") (pin "3") (pinfunction "M_3") (pintype "passive"))
      (node (ref "R3") (pin "2") (pinfunction "2_2") (pintype "passive"))
      (node (ref "RJ2") (pin "1") (pinfunction "1_1") (pintype "passive"))
    )
    (net (code "25") (name "LAMPA_CS") (class "Default")
      (node (ref "POTI") (pin "2") (pinfunction "2_2") (pintype "passive"))
      (node (ref "T2") (pin "1") (pinfunction "B_1") (pintype "passive"))
    )
    (net (code "26") (name "LAMPA_MAX") (class "Default")
      (node (ref "D17") (pin "C") (pinfunction "C_C") (pintype "passive"))
      (node (ref "POTI") (pin "3") (pinfunction "3_3") (pintype "passive"))
      (node (ref "R48") (pin "2") (pinfunction "2_2") (pintype "passive"))
    )
    (net (code "27") (name "LAMPA_MIN") (class "Default")
      (node (ref "POTI") (pin "1") (pinfunction "1_1") (pintype "passive"))
      (node (ref "R49") (pin "1") (pinfunction "1_1") (pintype "passive"))
    )
    (net (code "28") (name "MH") (class "Default")
      (node (ref "DIGIT") (pin "7") (pinfunction "7_7") (pintype "passive"))
      (node (ref "DIGIT") (pin "8") (pinfunction "8_8") (pintype "passive"))
      (node (ref "IC3") (pin "11") (pinfunction "A_11") (pintype "input"))
    )
    (net (code "29") (name "MIC_MUTE") (class "Default")
      (node (ref "D4") (pin "A") (pinfunction "A_A") (pintype "passive"))
      (node (ref "DIGIT") (pin "11") (pinfunction "11_11") (pintype "passive"))
      (node (ref "DIGIT") (pin "12") (pinfunction "12_12") (pintype "passive"))
    )
    (net (code "30") (name "MUTE") (class "Default")
      (node (ref "DIGIT") (pin "10") (pinfunction "10_10") (pintype "passive"))
      (node (ref "DIGIT") (pin "9") (pinfunction "9_9") (pintype "passive"))
      (node (ref "Q3") (pin "1") (pinfunction "G_1") (pintype "passive"))
    )
    (net (code "31") (name "N$49") (class "Default")
      (node (ref "IC3") (pin "14") (pinfunction "X_14") (pintype "bidirectional"))
      (node (ref "MUSOR/NORMAL") (pin "2") (pinfunction "2_2") (pintype "passive"))
      (node (ref "R30") (pin "2") (pinfunction "2_2") (pintype "passive"))
      (node (ref "SJ5") (pin "2") (pinfunction "2_2") (pintype "passive"))
    )
    (net (code "32") (name "N$50") (class "Default")
      (node (ref "IC3") (pin "15") (pinfunction "Y_15") (pintype "bidirectional"))
      (node (ref "R28") (pin "2") (pinfunction "2_2") (pintype "passive"))
      (node (ref "SJ4") (pin "2") (pinfunction "2_2") (pintype "passive"))
    )
    (net (code "33") (name "Net-(C1-Pad+)") (class "Default")
      (node (ref "C1") (pin "+") (pinfunction "+_+") (pintype "passive"))
      (node (ref "R1") (pin "1") (pinfunction "1_1") (pintype "passive"))
      (node (ref "R4") (pin "2") (pinfunction "2_2") (pintype "passive"))
    )
    (net (code "34") (name "Net-(C2-Pad2)") (class "Default")
      (node (ref "C2") (pin "2") (pinfunction "2_2") (pintype "passive"))
      (node (ref "R6") (pin "1") (pinfunction "1_1") (pintype "passive"))
    )
    (net (code "35") (name "Net-(C3-Pad2)") (class "Default")
      (node (ref "C3") (pin "2") (pinfunction "2_2") (pintype "passive"))
      (node (ref "R7") (pin "1") (pinfunction "1_1") (pintype "passive"))
    )
    (net (code "36") (name "Net-(C4-Pad2)") (class "Default")
      (node (ref "C4") (pin "2") (pinfunction "2_2") (pintype "passive"))
      (node (ref "R10") (pin "1") (pinfunction "1_1") (pintype "passive"))
    )
    (net (code "37") (name "Net-(C5-Pad2)") (class "Default")
      (node (ref "C5") (pin "2") (pinfunction "2_2") (pintype "passive"))
      (node (ref "R11") (pin "1") (pinfunction "1_1") (pintype "passive"))
      (node (ref "R8") (pin "2") (pinfunction "2_2") (pintype "passive"))
    )
    (net (code "38") (name "Net-(C6-Pad2)") (class "Default")
      (node (ref "C6") (pin "2") (pinfunction "2_2") (pintype "passive"))
      (node (ref "R8") (pin "1") (pinfunction "1_1") (pintype "passive"))
    )
    (net (code "39") (name "Net-(C11-Pad1)") (class "Default")
      (node (ref "C11") (pin "1") (pinfunction "1_1") (pintype "passive"))
      (node (ref "R16") (pin "2") (pinfunction "2_2") (pintype "passive"))
      (node (ref "R18") (pin "1") (pinfunction "1_1") (pintype "passive"))
    )
    (net (code "40") (name "Net-(C12-Pad1)") (class "Default")
      (node (ref "C12") (pin "1") (pinfunction "1_1") (pintype "passive"))
      (node (ref "R19") (pin "1") (pinfunction "1_1") (pintype "passive"))
    )
    (net (code "41") (name "Net-(C12-Pad2)") (class "Default")
      (node (ref "C12") (pin "2") (pinfunction "2_2") (pintype "passive"))
      (node (ref "D1") (pin "C") (pinfunction "C_C") (pintype "passive"))
      (node (ref "D2") (pin "A") (pinfunction "A_A") (pintype "passive"))
    )
    (net (code "42") (name "Net-(C13-Pad1)") (class "Default")
      (node (ref "C13") (pin "1") (pinfunction "1_1") (pintype "passive"))
      (node (ref "R17") (pin "2") (pinfunction "2_2") (pintype "passive"))
      (node (ref "R19") (pin "2") (pinfunction "2_2") (pintype "passive"))
    )
    (net (code "43") (name "Net-(C17-Pad1)") (class "Default")
      (node (ref "C17") (pin "1") (pinfunction "1_1") (pintype "passive"))
      (node (ref "D3") (pin "C") (pinfunction "C_C") (pintype "passive"))
      (node (ref "R27") (pin "2") (pinfunction "2_2") (pintype "passive"))
    )
    (net (code "44") (name "Net-(C20-Pad2)") (class "Default")
      (node (ref "C20") (pin "2") (pinfunction "2_2") (pintype "passive"))
      (node (ref "R34") (pin "1") (pinfunction "1_1") (pintype "passive"))
    )
    (net (code "45") (name "Net-(C21-Pad2)") (class "Default")
      (node (ref "C21") (pin "2") (pinfunction "2_2") (pintype "passive"))
      (node (ref "R35") (pin "1") (pinfunction "1_1") (pintype "passive"))
    )
    (net (code "46") (name "Net-(C54-Pad-)") (class "Default")
      (node (ref "C54") (pin "-") (pinfunction "-_-") (pintype "passive"))
      (node (ref "C55") (pin "2") (pinfunction "2_2") (pintype "passive"))
      (node (ref "D15") (pin "A") (pinfunction "A_A") (pintype "passive"))
      (node (ref "D19") (pin "A") (pinfunction "A_A") (pintype "passive"))
      (node (ref "SJ1") (pin "2") (pinfunction "2_2") (pintype "passive"))
      (node (ref "SJ7") (pin "1") (pinfunction "1_1") (pintype "passive"))
    )
    (net (code "47") (name "Net-(C63-Pad1)") (class "Default")
      (node (ref "C63") (pin "1") (pinfunction "1_1") (pintype "passive"))
      (node (ref "C65") (pin "+") (pinfunction "+_+") (pintype "passive"))
      (node (ref "L10") (pin "2") (pinfunction "2_2") (pintype "passive"))
      (node (ref "R52") (pin "2") (pinfunction "2_2") (pintype "passive"))
    )
    (net (code "48") (name "Net-(C64-Pad2)") (class "Default")
      (node (ref "C64") (pin "2") (pinfunction "2_2") (pintype "passive"))
      (node (ref "L11") (pin "2") (pinfunction "2_2") (pintype "passive"))
      (node (ref "L12") (pin "1") (pinfunction "1_1") (pintype "passive"))
      (node (ref "R53") (pin "1") (pinfunction "1_1") (pintype "passive"))
    )
    (net (code "49") (name "Net-(C66-Pad+)") (class "Default")
      (node (ref "C66") (pin "+") (pinfunction "+_+") (pintype "passive"))
      (node (ref "C70") (pin "2") (pinfunction "2_2") (pintype "passive"))
      (node (ref "L11") (pin "1") (pinfunction "1_1") (pintype "passive"))
    )
    (net (code "50") (name "Net-(C68-Pad1)") (class "Default")
      (node (ref "C68") (pin "1") (pinfunction "1_1") (pintype "passive"))
      (node (ref "SJ4") (pin "1") (pinfunction "1_1") (pintype "passive"))
    )
    (net (code "51") (name "Net-(C69-Pad1)") (class "Default")
      (node (ref "C69") (pin "1") (pinfunction "1_1") (pintype "passive"))
      (node (ref "SJ5") (pin "1") (pinfunction "1_1") (pintype "passive"))
    )
    (net (code "52") (name "Net-(C71-Pad1)") (class "Default")
      (node (ref "C71") (pin "1") (pinfunction "1_1") (pintype "passive"))
      (node (ref "R55") (pin "2") (pinfunction "2_2") (pintype "passive"))
      (node (ref "SD2") (pin "HACK") (pinfunction "HACK_HACK") (pintype "bidirectional"))
    )
    (net (code "53") (name "Net-(D3-PadA)") (class "Default")
      (node (ref "D3") (pin "A") (pinfunction "A_A") (pintype "passive"))
      (node (ref "R26") (pin "2") (pinfunction "2_2") (pintype "passive"))
    )
    (net (code "54") (name "Net-(D12-A)") (class "Default")
      (node (ref "D12") (pin "2") (pinfunction "A_2") (pintype "passive"))
      (node (ref "RJ2") (pin "8") (pinfunction "8_8") (pintype "passive"))
    )
    (net (code "55") (name "Net-(D13-A)") (class "Default")
      (node (ref "D13") (pin "2") (pinfunction "A_2") (pintype "passive"))
      (node (ref "DSUB1") (pin "8") (pinfunction "M_8") (pintype "passive"))
    )
    (net (code "56") (name "Net-(D14-C)") (class "Default")
      (node (ref "D14") (pin "1") (pinfunction "C_1") (pintype "passive"))
      (node (ref "JP1") (pin "1") (pinfunction "1_1") (pintype "passive"))
      (node (ref "L9") (pin "1") (pinfunction "1_1") (pintype "passive"))
    )
    (net (code "57") (name "Net-(D16-PadC)") (class "Default")
      (node (ref "D16") (pin "C") (pinfunction "C_C") (pintype "passive"))
      (node (ref "D17") (pin "A") (pinfunction "A_A") (pintype "passive"))
    )
    (net (code "58") (name "Net-(D18-PadA)") (class "Default")
      (node (ref "D18") (pin "A") (pinfunction "A_A") (pintype "passive"))
      (node (ref "D19") (pin "C") (pinfunction "C_C") (pintype "passive"))
      (node (ref "R55") (pin "1") (pinfunction "1_1") (pintype "passive"))
    )
    (net (code "59") (name "Net-(F2-Pad2)") (class "Default")
      (node (ref "F2") (pin "2") (pinfunction "2_2") (pintype "passive"))
      (node (ref "L7") (pin "1") (pinfunction "1_1") (pintype "passive"))
    )
    (net (code "60") (name "Net-(F_LED-Pad2)") (class "Default")
      (node (ref "F_LED") (pin "2") (pinfunction "2_2") (pintype "passive"))
      (node (ref "R27") (pin "1") (pinfunction "1_1") (pintype "passive"))
    )
    (net (code "61") (name "Net-(HP_KIB-S)") (class "Default")
      (node (ref "C66") (pin "-") (pinfunction "-_-") (pintype "passive"))
      (node (ref "HP_KI") (pin "2") (pinfunction "S_2") (pintype "passive"))
      (node (ref "R56") (pin "1") (pinfunction "1_1") (pintype "passive"))
    )
    (net (code "62") (name "Net-(IC1A-+IN)") (class "Default")
      (node (ref "C10") (pin "1") (pinfunction "1_1") (pintype "passive"))
      (node (ref "IC1") (pin "3") (pinfunction "+IN_3") (pintype "input"))
      (node (ref "R10") (pin "2") (pinfunction "2_2") (pintype "passive"))
      (node (ref "R14") (pin "2") (pinfunction "2_2") (pintype "passive"))
    )
    (net (code "63") (name "Net-(IC1A--IN)") (class "Default")
      (node (ref "C6") (pin "1") (pinfunction "1_1") (pintype "passive"))
      (node (ref "C8") (pin "2") (pinfunction "2_2") (pintype "passive"))
      (node (ref "IC1") (pin "2") (pinfunction "-IN_2") (pintype "input"))
      (node (ref "R11") (pin "2") (pinfunction "2_2") (pintype "passive"))
      (node (ref "R12") (pin "1") (pinfunction "1_1") (pintype "passive"))
    )
    (net (code "64") (name "Net-(IC1B-+IN)") (class "Default")
      (node (ref "FENYELL") (pin "2") (pinfunction "2_2") (pintype "passive"))
      (node (ref "IC1") (pin "5") (pinfunction "+IN_5") (pintype "input"))
      (node (ref "Q1") (pin "3") (pinfunction "D_3") (pintype "passive"))
      (node (ref "R18") (pin "2") (pinfunction "2_2") (pintype "passive"))
    )
    (net (code "65") (name "Net-(IC1B--IN)") (class "Default")
      (node (ref "C14") (pin "2") (pinfunction "2_2") (pintype "passive"))
      (node (ref "IC1") (pin "6") (pinfunction "-IN_6") (pintype "input"))
      (node (ref "R20") (pin "2") (pinfunction "2_2") (pintype "passive"))
      (node (ref "R21") (pin "1") (pinfunction "1_1") (pintype "passive"))
    )
    (net (code "66") (name "Net-(IC1B-OUT)") (class "Default")
      (node (ref "C14") (pin "1") (pinfunction "1_1") (pintype "passive"))
      (node (ref "C15") (pin "2") (pinfunction "2_2") (pintype "passive"))
      (node (ref "IC1") (pin "7") (pinfunction "OUT_7") (pintype "output"))
      (node (ref "IC2") (pin "3") (pinfunction "+IN_3") (pintype "input"))
      (node (ref "R21") (pin "2") (pinfunction "2_2") (pintype "passive"))
    )
    (net (code "67") (name "Net-(IC2A--IN)") (class "Default")
      (node (ref "C16") (pin "2") (pinfunction "2_2") (pintype "passive"))
      (node (ref "IC2") (pin "2") (pinfunction "-IN_2") (pintype "input"))
      (node (ref "R22") (pin "2") (pinfunction "2_2") (pintype "passive"))
      (node (ref "R23") (pin "1") (pinfunction "1_1") (pintype "passive"))
    )
    (net (code "68") (name "Net-(IC2A-OUT)") (class "Default")
      (node (ref "C16") (pin "1") (pinfunction "1_1") (pintype "passive"))
      (node (ref "IC2") (pin "1") (pinfunction "OUT_1") (pintype "output"))
      (node (ref "LED1") (pin "K") (pinfunction "C_K") (pintype "passive"))
      (node (ref "R25") (pin "2") (pinfunction "2_2") (pintype "passive"))
      (node (ref "R26") (pin "1") (pinfunction "1_1") (pintype "passive"))
    )
    (net (code "69") (name "Net-(IC2B-+IN)") (class "Default")
      (node (ref "C7") (pin "1") (pinfunction "1_1") (pintype "passive"))
      (node (ref "IC2") (pin "5") (pinfunction "+IN_5") (pintype "input"))
      (node (ref "R6") (pin "2") (pinfunction "2_2") (pintype "passive"))
      (node (ref "R9") (pin "2") (pinfunction "2_2") (pintype "passive"))
    )
    (net (code "70") (name "Net-(IC2B--IN)") (class "Default")
      (node (ref "C9") (pin "2") (pinfunction "2_2") (pintype "passive"))
      (node (ref "IC2") (pin "6") (pinfunction "-IN_6") (pintype "input"))
      (node (ref "R13") (pin "1") (pinfunction "1_1") (pintype "passive"))
      (node (ref "R7") (pin "2") (pinfunction "2_2") (pintype "passive"))
    )
    (net (code "71") (name "Net-(IC2B-OUT)") (class "Default")
      (node (ref "C9") (pin "1") (pinfunction "1_1") (pintype "passive"))
      (node (ref "IC2") (pin "7") (pinfunction "OUT_7") (pintype "output"))
      (node (ref "R13") (pin "2") (pinfunction "2_2") (pintype "passive"))
      (node (ref "R17") (pin "1") (pinfunction "1_1") (pintype "passive"))
    )
    (net (code "72") (name "Net-(IC3A-INH)") (class "Default")
      (node (ref "IC3") (pin "6") (pinfunction "INH_6") (pintype "input"))
      (node (ref "Q3") (pin "3") (pinfunction "D_3") (pintype "passive"))
      (node (ref "R54") (pin "1") (pinfunction "1_1") (pintype "passive"))
    )
    (net (code "73") (name "Net-(IC3A-Y0)") (class "Default")
      (node (ref "IC3") (pin "2") (pinfunction "Y0_2") (pintype "bidirectional"))
      (node (ref "IC3") (pin "4") (pinfunction "Z_4") (pintype "bidirectional"))
    )
    (net (code "74") (name "Net-(IC4A-+IN)") (class "Default")
      (node (ref "C15") (pin "1") (pinfunction "1_1") (pintype "passive"))
      (node (ref "IC4") (pin "3") (pinfunction "+IN_3") (pintype "input"))
      (node (ref "R24") (pin "2") (pinfunction "2_2") (pintype "passive"))
      (node (ref "R29") (pin "2") (pinfunction "2_2") (pintype "passive"))
    )
    (net (code "75") (name "Net-(IC4A--IN)") (class "Default")
      (node (ref "C18") (pin "2") (pinfunction "2_2") (pintype "passive"))
      (node (ref "IC4") (pin "2") (pinfunction "-IN_2") (pintype "input"))
      (node (ref "R31") (pin "2") (pinfunction "2_2") (pintype "passive"))
      (node (ref "R32") (pin "1") (pinfunction "1_1") (pintype "passive"))
    )
    (net (code "76") (name "Net-(IC4A-OUT)") (class "Default")
      (node (ref "C18") (pin "1") (pinfunction "1_1") (pintype "passive"))
      (node (ref "C20") (pin "1") (pinfunction "1_1") (pintype "passive"))
      (node (ref "IC4") (pin "1") (pinfunction "OUT_1") (pintype "output"))
      (node (ref "R32") (pin "2") (pinfunction "2_2") (pintype "passive"))
    )
    (net (code "77") (name "Net-(IC4B--IN)") (class "Default")
      (node (ref "C19") (pin "2") (pinfunction "2_2") (pintype "passive"))
      (node (ref "IC4") (pin "6") (pinfunction "-IN_6") (pintype "input"))
      (node (ref "R29") (pin "1") (pinfunction "1_1") (pintype "passive"))
      (node (ref "R33") (pin "1") (pinfunction "1_1") (pintype "passive"))
    )
    (net (code "78") (name "Net-(IC4B-OUT)") (class "Default")
      (node (ref "C19") (pin "1") (pinfunction "1_1") (pintype "passive"))
      (node (ref "C21") (pin "1") (pinfunction "1_1") (pintype "passive"))
      (node (ref "IC4") (pin "7") (pinfunction "OUT_7") (pintype "output"))
      (node (ref "R33") (pin "2") (pinfunction "2_2") (pintype "passive"))
    )
    (net (code "79") (name "Net-(IC11-BSL)") (class "Default")
      (node (ref "C61") (pin "1") (pinfunction "1_1") (pintype "passive"))
      (node (ref "IC11") (pin "21") (pinfunction "BSL_21") (pintype "passive"))
    )
    (net (code "80") (name "Net-(IC11-BSR)") (class "Default")
      (node (ref "C60") (pin "1") (pinfunction "1_1") (pintype "passive"))
      (node (ref "IC11") (pin "16") (pinfunction "BSR_16") (pintype "passive"))
    )
    (net (code "81") (name "Net-(IC11-BYPASS)") (class "Default")
      (node (ref "C56") (pin "1") (pinfunction "1_1") (pintype "passive"))
      (node (ref "IC11") (pin "7") (pinfunction "BYPASS_7") (pintype "input"))
    )
    (net (code "82") (name "Net-(IC11-GAIN0)") (class "Default")
      (node (ref "IC11") (pin "18") (pinfunction "GAIN0_18") (pintype "input"))
      (node (ref "SJ2") (pin "2") (pinfunction "2_2") (pintype "passive"))
    )
    (net (code "83") (name "Net-(IC11-LIN)") (class "Default")
      (node (ref "C69") (pin "2") (pinfunction "2_2") (pintype "passive"))
      (node (ref "IC11") (pin "5") (pinfunction "LIN_5") (pintype "input"))
    )
    (net (code "84") (name "Net-(IC11-MUTE)") (class "Default")
      (node (ref "IC11") (pin "4") (pinfunction "MUTE_4") (pintype "input"))
      (node (ref "SJ8") (pin "1") (pinfunction "1_1") (pintype "passive"))
    )
    (net (code "85") (name "Net-(IC11-RIN)") (class "Default")
      (node (ref "C68") (pin "2") (pinfunction "2_2") (pintype "passive"))
      (node (ref "IC11") (pin "6") (pinfunction "RIN_6") (pintype "input"))
    )
    (net (code "86") (name "Net-(IC11-VCLAMP)") (class "Default")
      (node (ref "C59") (pin "1") (pinfunction "1_1") (pintype "passive"))
      (node (ref "IC11") (pin "11") (pinfunction "VCLAMP_11") (pintype "input"))
    )
    (net (code "87") (name "Net-(LAMPAB-S)") (class "Default")
      (node (ref "LAMPA") (pin "2") (pinfunction "S_2") (pintype "passive"))
      (node (ref "T2") (pin "2") (pinfunction "C_2") (pintype "passive"))
    )
    (net (code "88") (name "Net-(LED1-PadA)") (class "Default")
      (node (ref "LED1") (pin "A") (pinfunction "A_A") (pintype "passive"))
      (node (ref "R23") (pin "2") (pinfunction "2_2") (pintype "passive"))
      (node (ref "R25") (pin "1") (pinfunction "1_1") (pintype "passive"))
    )
    (net (code "89") (name "Net-(PROG-Pad4)") (class "Default")
      (node (ref "PROG") (pin "4") (pinfunction "4_4") (pintype "passive"))
      (node (ref "R36") (pin "2") (pinfunction "2_2") (pintype "passive"))
    )
    (net (code "90") (name "Net-(PROG-Pad8)") (class "Default")
      (node (ref "PROG") (pin "8") (pinfunction "8_8") (pintype "passive"))
      (node (ref "R37") (pin "2") (pinfunction "2_2") (pintype "passive"))
    )
    (net (code "91") (name "Net-(Q1-G)") (class "Default")
      (node (ref "D4") (pin "C") (pinfunction "C_C") (pintype "passive"))
      (node (ref "Q1") (pin "1") (pinfunction "G_1") (pintype "passive"))
      (node (ref "R38") (pin "2") (pinfunction "2_2") (pintype "passive"))
    )
    (net (code "92") (name "Net-(SD2-CTRL)") (class "Default")
      (node (ref "C48") (pin "1") (pinfunction "1_1") (pintype "passive"))
      (node (ref "C49") (pin "+") (pinfunction "+_+") (pintype "passive"))
      (node (ref "R47") (pin "2") (pinfunction "2_2") (pintype "passive"))
      (node (ref "SD2") (pin "CONTROL") (pinfunction "CTRL_CONTROL") (pintype "bidirectional"))
    )
    (net (code "93") (name "Net-(SD2-IN+)") (class "Default")
      (node (ref "C22") (pin "+") (pinfunction "+_+") (pintype "passive"))
      (node (ref "C47") (pin "+") (pinfunction "+_+") (pintype "passive"))
      (node (ref "L7") (pin "2") (pinfunction "2_2") (pintype "passive"))
      (node (ref "SD2") (pin "INPUT+") (pinfunction "IN+_INPUT+") (pintype "bidirectional"))
    )
    (net (code "94") (name "Net-(SD2-IN-)") (class "Default")
      (node (ref "C22") (pin "-") (pinfunction "-_-") (pintype "passive"))
      (node (ref "C47") (pin "-") (pinfunction "-_-") (pintype "passive"))
      (node (ref "C48") (pin "2") (pinfunction "2_2") (pintype "passive"))
      (node (ref "C49") (pin "-") (pinfunction "-_-") (pintype "passive"))
      (node (ref "L8") (pin "2") (pinfunction "2_2") (pintype "passive"))
      (node (ref "R47") (pin "1") (pinfunction "1_1") (pintype "passive"))
      (node (ref "SD2") (pin "INPUT-") (pinfunction "IN-_INPUT-") (pintype "bidirectional"))
    )
    (net (code "95") (name "Net-(SD2-PadOUT-)") (class "Default")
      (node (ref "SD2") (pin "OUT-") (pinfunction "OUT-_OUT-") (pintype "bidirectional"))
      (node (ref "SJ7") (pin "2") (pinfunction "2_2") (pintype "passive"))
    )
    (net (code "96") (name "Net-(SP_KIB-S)") (class "Default")
      (node (ref "C65") (pin "-") (pinfunction "-_-") (pintype "passive"))
      (node (ref "SP_KI") (pin "2") (pinfunction "S_2") (pintype "passive"))
    )
    (net (code "97") (name "Net-(T2-E)") (class "Default")
      (node (ref "R50") (pin "1") (pinfunction "1_1") (pintype "passive"))
      (node (ref "T2") (pin "3") (pinfunction "E_3") (pintype "passive"))
    )
    (net (code "98") (name "OUT+") (class "Default")
      (node (ref "DSUB1") (pin "4") (pinfunction "M_4") (pintype "passive"))
      (node (ref "R34") (pin "2") (pinfunction "2_2") (pintype "passive"))
      (node (ref "RJ2") (pin "6") (pinfunction "6_6") (pintype "passive"))
    )
    (net (code "99") (name "OUT-") (class "Default")
      (node (ref "DSUB1") (pin "5") (pinfunction "M_5") (pintype "passive"))
      (node (ref "R35") (pin "2") (pinfunction "2_2") (pintype "passive"))
      (node (ref "RJ2") (pin "3") (pinfunction "3_3") (pintype "passive"))
    )
    (net (code "100") (name "POTI_JEL") (class "Default")
      (node (ref "C13") (pin "2") (pinfunction "2_2") (pintype "passive"))
      (node (ref "POTI") (pin "7") (pinfunction "7_7") (pintype "passive"))
      (node (ref "POTI") (pin "8") (pinfunction "8_8") (pintype "passive"))
    )
    (net (code "101") (name "SP") (class "Default")
      (node (ref "MUSOR/NORMAL") (pin "5") (pinfunction "5_5") (pintype "passive"))
      (node (ref "POTI") (pin "10") (pinfunction "10_10") (pintype "passive"))
      (node (ref "POTI") (pin "9") (pinfunction "9_9") (pintype "passive"))
    )
    (net (code "102") (name "SPM") (class "Default")
      (node (ref "DIGIT") (pin "5") (pinfunction "5_5") (pintype "passive"))
      (node (ref "DIGIT") (pin "6") (pinfunction "6_6") (pintype "passive"))
      (node (ref "IC3") (pin "10") (pinfunction "B_10") (pintype "input"))
    )
    (net (code "103") (name "SPOUT") (class "Default")
      (node (ref "C60") (pin "2") (pinfunction "2_2") (pintype "passive"))
      (node (ref "C71") (pin "2") (pinfunction "2_2") (pintype "passive"))
      (node (ref "IC11") (pin "15") (pinfunction "ROUT_15") (pintype "output"))
      (node (ref "L10") (pin "1") (pinfunction "1_1") (pintype "passive"))
    )
    (net (code "104") (name "VDD") (class "Default")
      (node (ref "C26") (pin "1") (pinfunction "1_1") (pintype "passive"))
      (node (ref "C57") (pin "+") (pinfunction "+_+") (pintype "passive"))
      (node (ref "C58") (pin "1") (pinfunction "1_1") (pintype "passive"))
      (node (ref "IC1") (pin "8") (pinfunction "V+_8") (pintype "power_in"))
      (node (ref "IC11") (pin "19") (pinfunction "AVCC_19") (pintype "input"))
      (node (ref "IC11") (pin "20") (pinfunction "AVCC_20") (pintype "input"))
      (node (ref "IC2") (pin "8") (pinfunction "V+_8") (pintype "power_in"))
      (node (ref "IC4") (pin "8") (pinfunction "V+_8") (pintype "power_in"))
      (node (ref "R1") (pin "2") (pinfunction "2_2") (pintype "passive"))
      (node (ref "R51") (pin "1") (pinfunction "1_1") (pintype "passive"))
      (node (ref "SJ2") (pin "1") (pinfunction "1_1") (pintype "passive"))
    )
    (net (code "105") (name "VSS") (class "Default")
      (node (ref "C27") (pin "2") (pinfunction "2_2") (pintype "passive"))
      (node (ref "IC1") (pin "4") (pinfunction "V-_4") (pintype "power_in"))
      (node (ref "IC2") (pin "4") (pinfunction "V-_4") (pintype "power_in"))
      (node (ref "IC3") (pin "7") (pinfunction "VEE_7") (pintype "power_in"))
      (node (ref "IC4") (pin "4") (pinfunction "V-_4") (pintype "power_in"))
      (node (ref "SJ1") (pin "1") (pinfunction "1_1") (pintype "passive"))
    )
    (net (code "106") (name "X0") (class "Default")
      (node (ref "IC3") (pin "12") (pinfunction "X0_12") (pintype "bidirectional"))
      (node (ref "MUSOR/NORMAL") (pin "3") (pinfunction "3_3") (pintype "passive"))
    )
    (net (code "107") (name "unconnected-(IC12-GND-Pad2)") (class "Default")
      (node (ref "IC12") (pin "2") (pinfunction "GND_2") (pintype "passive"))
    )
    (net (code "108") (name "unconnected-(IC12-VI-Pad1)") (class "Default")
      (node (ref "IC12") (pin "1") (pinfunction "VI_1") (pintype "input"))
    )
    (net (code "109") (name "unconnected-(IC12-VO-Pad3)") (class "Default")
      (node (ref "IC12") (pin "3") (pinfunction "VO_3") (pintype "passive"))
    )
    (net (code "110") (name "unconnected-(POTI-Pad4)") (class "Default")
      (node (ref "POTI") (pin "4") (pinfunction "4_4") (pintype "passive"))
    )
    (net (code "111") (name "unconnected-(SD2-PadSZAB)") (class "Default")
      (node (ref "SD2") (pin "SZAB") (pinfunction "SZAB_SZAB") (pintype "bidirectional"))
    )
    (net (code "112") (name "~{MCLR}") (class "Default")
      (node (ref "PROG") (pin "5") (pinfunction "5_5") (pintype "passive"))
      (node (ref "TAP") (pin "1") (pinfunction "1_1") (pintype "passive"))
      (node (ref "TAP") (pin "2") (pinfunction "2_2") (pintype "passive"))
    )
  )
)
